# connector.net
KiCad netlist of a schematic drawn in Altium Designer
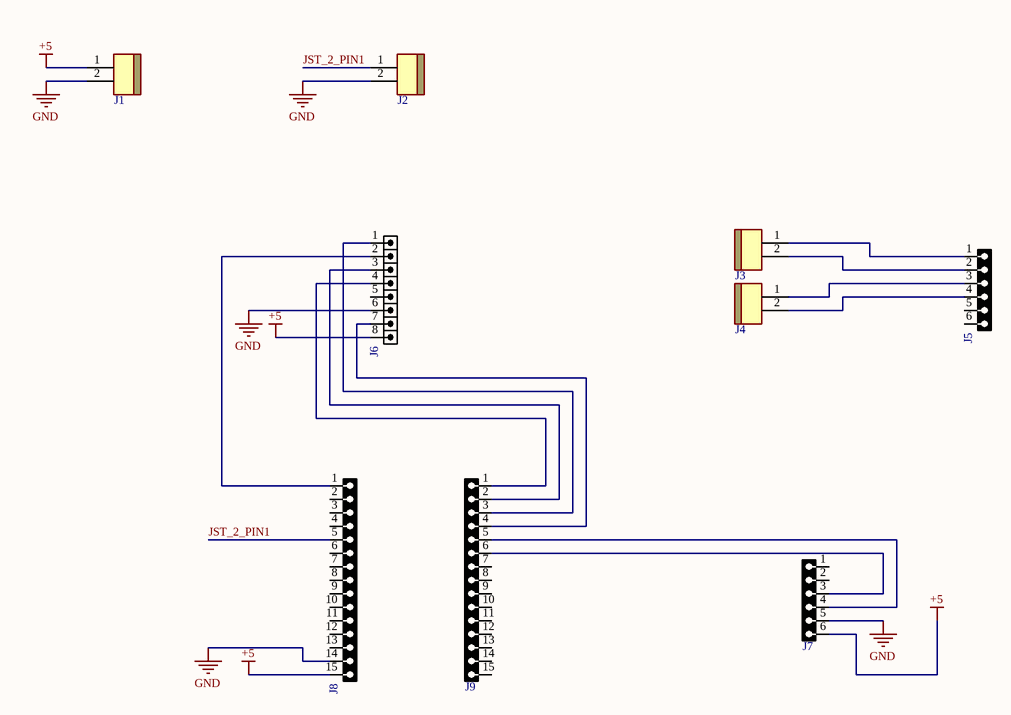
[diagram p0: connector.SchDoc]

(export (version "E")
  (design (tool "Eeschema 10.0.6"))
  (components
    (comp (ref "J1")
      (value "JST BxB-PH-K 2Pin")
      (footprint "JST B2B-PH-K")
      (description "Connector Header Through Hole 0.079\" (2.00mm)")
      (fields (field (name "PARTNUMBER") "B2B-PH-K-S(LF)(SN)"))
      (libsource (lib "") (part "JST BxB-PH-K 2Pin_1"))
    )
    (comp (ref "J2")
      (value "JST BxB-PH-K 2Pin")
      (footprint "JST B2B-PH-K")
      (description "Connector Header Through Hole 0.079\" (2.00mm)")
      (fields (field (name "PARTNUMBER") "B2B-PH-K-S(LF)(SN)"))
      (libsource (lib "") (part "JST BxB-PH-K 2Pin_1"))
    )
    (comp (ref "J3")
      (value "JST BxB-PH-K 2Pin")
      (footprint "JST B2B-PH-K")
      (description "Connector Header Through Hole 0.079\" (2.00mm)")
      (fields (field (name "PARTNUMBER") "B2B-PH-K-S(LF)(SN)"))
      (libsource (lib "Conn Terminal") (part "JST BxB-PH-K 2Pin"))
    )
    (comp (ref "J4")
      (value "JST BxB-PH-K 2Pin")
      (footprint "JST B2B-PH-K")
      (description "Connector Header Through Hole 0.079\" (2.00mm)")
      (fields (field (name "PARTNUMBER") "B2B-PH-K-S(LF)(SN)"))
      (libsource (lib "Conn Terminal") (part "JST BxB-PH-K 2Pin"))
    )
    (comp (ref "J5")
      (value "HDRF6")
      (footprint "HDRLP_F_1X6")
      (description "CONN, HEADER, Male, pitch: 2.54mm, 6POS")
      (libsource (lib "Conn Header") (part "HDRLP_F_1X6"))
    )
    (comp (ref "J6")
      (value "HDRM8")
      (footprint "HDRLP_M_1X8")
      (description "CONN, HEADER, Male, pitch: 2.54mm, 8POS")
      (libsource (lib "Conn Header") (part "HDRLP_M_1X8"))
    )
    (comp (ref "J7")
      (value "HDRF6")
      (footprint "HDRLP_F_1X6")
      (description "CONN, HEADER, Male, pitch: 2.54mm, 6POS")
      (libsource (lib "") (part "HDRLP_F_1X6_1"))
    )
    (comp (ref "J8")
      (value "HDRF15")
      (footprint "HDR_F_1X15")
      (description "CONN, HEADER, Female, pitch: 2.54mm, 15POS")
      (libsource (lib "Conn Header") (part "HDR_F_1X15"))
    )
    (comp (ref "J9")
      (value "HDRF15")
      (footprint "HDR_F_1X15")
      (description "CONN, HEADER, Female, pitch: 2.54mm, 15POS")
      (libsource (lib "Conn Header") (part "HDR_F_1X15"))
    )
  )
  (nets
    (net (code "1") (name "+5") (class "Default")
      (node (ref "J1") (pin "1") (pinfunction "1_1") (pintype "passive"))
      (node (ref "J6") (pin "8") (pinfunction "8_8") (pintype "passive"))
      (node (ref "J7") (pin "6") (pinfunction "6_6") (pintype "passive"))
      (node (ref "J8") (pin "15") (pinfunction "15_15") (pintype "passive"))
    )
    (net (code "2") (name "/JST_2_PIN1") (class "Default")
      (node (ref "J2") (pin "1") (pinfunction "1_1") (pintype "passive"))
      (node (ref "J8") (pin "5") (pinfunction "5_5") (pintype "passive"))
    )
    (net (code "3") (name "GND") (class "Default")
      (node (ref "J1") (pin "2") (pinfunction "2_2") (pintype "passive"))
      (node (ref "J2") (pin "2") (pinfunction "2_2") (pintype "passive"))
      (node (ref "J6") (pin "6") (pinfunction "6_6") (pintype "passive"))
      (node (ref "J7") (pin "5") (pinfunction "5_5") (pintype "passive"))
      (node (ref "J8") (pin "14") (pinfunction "14_14") (pintype "passive"))
    )
    (net (code "4") (name "Net-(J3-Pad1)") (class "Default")
      (node (ref "J3") (pin "1") (pinfunction "1_1") (pintype "passive"))
      (node (ref "J5") (pin "1") (pinfunction "1_1") (pintype "passive"))
    )
    (net (code "5") (name "Net-(J3-Pad2)") (class "Default")
      (node (ref "J3") (pin "2") (pinfunction "2_2") (pintype "passive"))
      (node (ref "J5") (pin "2") (pinfunction "2_2") (pintype "passive"))
    )
    (net (code "6") (name "Net-(J4-Pad1)") (class "Default")
      (node (ref "J4") (pin "1") (pinfunction "1_1") (pintype "passive"))
      (node (ref "J5") (pin "3") (pinfunction "3_3") (pintype "passive"))
    )
    (net (code "7") (name "Net-(J4-Pad2)") (class "Default")
      (node (ref "J4") (pin "2") (pinfunction "2_2") (pintype "passive"))
      (node (ref "J5") (pin "4") (pinfunction "4_4") (pintype "passive"))
    )
    (net (code "8") (name "Net-(J6-Pad1)") (class "Default")
      (node (ref "J6") (pin "1") (pinfunction "1_1") (pintype "passive"))
      (node (ref "J9") (pin "3") (pinfunction "3_3") (pintype "passive"))
    )
    (net (code "9") (name "Net-(J6-Pad2)") (class "Default")
      (node (ref "J6") (pin "2") (pinfunction "2_2") (pintype "passive"))
      (node (ref "J8") (pin "1") (pinfunction "1_1") (pintype "passive"))
    )
    (net (code "10") (name "Net-(J6-Pad3)") (class "Default")
      (node (ref "J6") (pin "3") (pinfunction "3_3") (pintype "passive"))
      (node (ref "J9") (pin "2") (pinfunction "2_2") (pintype "passive"))
    )
    (net (code "11") (name "Net-(J6-Pad4)") (class "Default")
      (node (ref "J6") (pin "4") (pinfunction "4_4") (pintype "passive"))
      (node (ref "J9") (pin "1") (pinfunction "1_1") (pintype "passive"))
    )
    (net (code "12") (name "Net-(J6-Pad7)") (class "Default")
      (node (ref "J6") (pin "7") (pinfunction "7_7") (pintype "passive"))
      (node (ref "J9") (pin "4") (pinfunction "4_4") (pintype "passive"))
    )
    (net (code "13") (name "Net-(J7-Pad3)") (class "Default")
      (node (ref "J7") (pin "3") (pinfunction "3_3") (pintype "passive"))
      (node (ref "J9") (pin "6") (pinfunction "6_6") (pintype "passive"))
    )
    (net (code "14") (name "Net-(J7-Pad4)") (class "Default")
      (node (ref "J7") (pin "4") (pinfunction "4_4") (pintype "passive"))
      (node (ref "J9") (pin "5") (pinfunction "5_5") (pintype "passive"))
    )
    (net (code "15") (name "unconnected-(J5-Pad5)") (class "Default")
      (node (ref "J5") (pin "5") (pinfunction "5_5") (pintype "passive"))
    )
    (net (code "16") (name "unconnected-(J5-Pad6)") (class "Default")
      (node (ref "J5") (pin "6") (pinfunction "6_6") (pintype "passive"))
    )
    (net (code "17") (name "unconnected-(J6-Pad5)") (class "Default")
      (node (ref "J6") (pin "5") (pinfunction "5_5") (pintype "passive"))
    )
    (net (code "18") (name "unconnected-(J7-Pad1)") (class "Default")
      (node (ref "J7") (pin "1") (pinfunction "1_1") (pintype "passive"))
    )
    (net (code "19") (name "unconnected-(J7-Pad2)") (class "Default")
      (node (ref "J7") (pin "2") (pinfunction "2_2") (pintype "passive"))
    )
    (net (code "20") (name "unconnected-(J8-Pad2)") (class "Default")
      (node (ref "J8") (pin "2") (pinfunction "2_2") (pintype "passive"))
    )
    (net (code "21") (name "unconnected-(J8-Pad3)") (class "Default")
      (node (ref "J8") (pin "3") (pinfunction "3_3") (pintype "passive"))
    )
    (net (code "22") (name "unconnected-(J8-Pad4)") (class "Default")
      (node (ref "J8") (pin "4") (pinfunction "4_4") (pintype "passive"))
    )
    (net (code "23") (name "unconnected-(J8-Pad6)") (class "Default")
      (node (ref "J8") (pin "6") (pinfunction "6_6") (pintype "passive"))
    )
    (net (code "24") (name "unconnected-(J8-Pad7)") (class "Default")
      (node (ref "J8") (pin "7") (pinfunction "7_7") (pintype "passive"))
    )
    (net (code "25") (name "unconnected-(J8-Pad8)") (class "Default")
      (node (ref "J8") (pin "8") (pinfunction "8_8") (pintype "passive"))
    )
    (net (code "26") (name "unconnected-(J8-Pad9)") (class "Default")
      (node (ref "J8") (pin "9") (pinfunction "9_9") (pintype "passive"))
    )
    (net (code "27") (name "unconnected-(J8-Pad10)") (class "Default")
      (node (ref "J8") (pin "10") (pinfunction "10_10") (pintype "passive"))
    )
    (net (code "28") (name "unconnected-(J8-Pad11)") (class "Default")
      (node (ref "J8") (pin "11") (pinfunction "11_11") (pintype "passive"))
    )
    (net (code "29") (name "unconnected-(J8-Pad12)") (class "Default")
      (node (ref "J8") (pin "12") (pinfunction "12_12") (pintype "passive"))
    )
    (net (code "30") (name "unconnected-(J8-Pad13)") (class "Default")
      (node (ref "J8") (pin "13") (pinfunction "13_13") (pintype "passive"))
    )
    (net (code "31") (name "unconnected-(J9-Pad7)") (class "Default")
      (node (ref "J9") (pin "7") (pinfunction "7_7") (pintype "passive"))
    )
    (net (code "32") (name "unconnected-(J9-Pad8)") (class "Default")
      (node (ref "J9") (pin "8") (pinfunction "8_8") (pintype "passive"))
    )
    (net (code "33") (name "unconnected-(J9-Pad9)") (class "Default")
      (node (ref "J9") (pin "9") (pinfunction "9_9") (pintype "passive"))
    )
    (net (code "34") (name "unconnected-(J9-Pad10)") (class "Default")
      (node (ref "J9") (pin "10") (pinfunction "10_10") (pintype "passive"))
    )
    (net (code "35") (name "unconnected-(J9-Pad11)") (class "Default")
      (node (ref "J9") (pin "11") (pinfunction "11_11") (pintype "passive"))
    )
    (net (code "36") (name "unconnected-(J9-Pad12)") (class "Default")
      (node (ref "J9") (pin "12") (pinfunction "12_12") (pintype "passive"))
    )
    (net (code "37") (name "unconnected-(J9-Pad13)") (class "Default")
      (node (ref "J9") (pin "13") (pinfunction "13_13") (pintype "passive"))
    )
    (net (code "38") (name "unconnected-(J9-Pad14)") (class "Default")
      (node (ref "J9") (pin "14") (pinfunction "14_14") (pintype "passive"))
    )
    (net (code "39") (name "unconnected-(J9-Pad15)") (class "Default")
      (node (ref "J9") (pin "15") (pinfunction "15_15") (pintype "passive"))
    )
  )
)
